# Linkwitz_Riley.net
KiCad netlist of a schematic drawn in Altium Designer
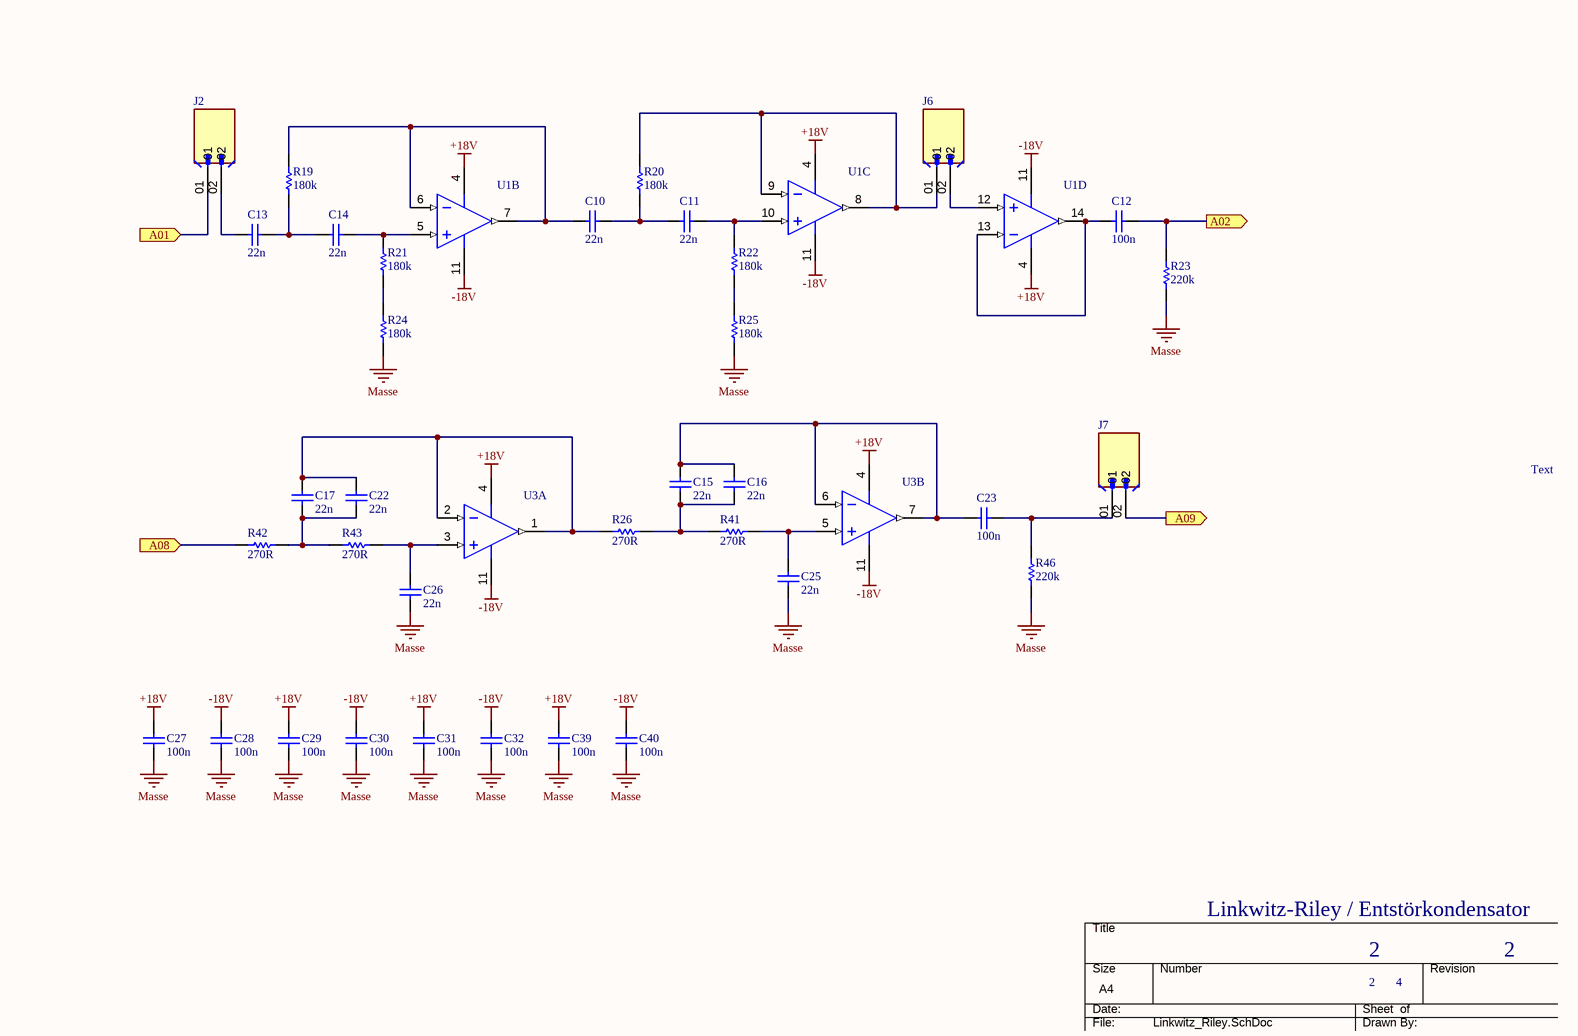
[diagram p0: Linkwitz_Riley.SchDoc]

(export (version "E")
  (design (tool "Eeschema 10.0.6"))
  (components
    (comp (ref "C10")
      (value "22n")
      (footprint "0805")
      (description "0805 Kondensator")
      (libsource (lib "Bauteile") (part "0805 Kondensator"))
    )
    (comp (ref "C11")
      (value "22n")
      (footprint "0805")
      (description "0805 Kondensator")
      (libsource (lib "Bauteile") (part "0805 Kondensator"))
    )
    (comp (ref "C12")
      (value "100n")
      (footprint "0805")
      (description "0805 Kondensator")
      (libsource (lib "Bauteile") (part "0805 Kondensator"))
    )
    (comp (ref "C13")
      (value "22n")
      (footprint "0805")
      (description "0805 Kondensator")
      (libsource (lib "Bauteile") (part "0805 Kondensator"))
    )
    (comp (ref "C14")
      (value "22n")
      (footprint "0805")
      (description "0805 Kondensator")
      (libsource (lib "Bauteile") (part "0805 Kondensator"))
    )
    (comp (ref "C15")
      (value "22n")
      (footprint "0805")
      (description "0805 Kondensator")
      (libsource (lib "Bauteile") (part "0805 Kondensator"))
    )
    (comp (ref "C16")
      (value "22n")
      (footprint "0805")
      (description "0805 Kondensator")
      (libsource (lib "Bauteile") (part "0805 Kondensator"))
    )
    (comp (ref "C17")
      (value "22n")
      (footprint "0805")
      (description "0805 Kondensator")
      (libsource (lib "Bauteile") (part "0805 Kondensator"))
    )
    (comp (ref "C22")
      (value "22n")
      (footprint "0805")
      (description "0805 Kondensator")
      (libsource (lib "Bauteile") (part "0805 Kondensator"))
    )
    (comp (ref "C23")
      (value "100n")
      (footprint "0805")
      (description "0805 Kondensator")
      (libsource (lib "Bauteile") (part "0805 Kondensator"))
    )
    (comp (ref "C25")
      (value "22n")
      (footprint "0805")
      (description "0805 Kondensator")
      (libsource (lib "Bauteile") (part "0805 Kondensator"))
    )
    (comp (ref "C26")
      (value "22n")
      (footprint "0805")
      (description "0805 Kondensator")
      (libsource (lib "Bauteile") (part "0805 Kondensator"))
    )
    (comp (ref "C27")
      (value "100n")
      (footprint "0805")
      (description "0805 Kondensator")
      (libsource (lib "Bauteile") (part "0805 Kondensator"))
    )
    (comp (ref "C28")
      (value "100n")
      (footprint "0805")
      (description "0805 Kondensator")
      (libsource (lib "Bauteile") (part "0805 Kondensator"))
    )
    (comp (ref "C29")
      (value "100n")
      (footprint "0805")
      (description "0805 Kondensator")
      (libsource (lib "Bauteile") (part "0805 Kondensator"))
    )
    (comp (ref "C30")
      (value "100n")
      (footprint "0805")
      (description "0805 Kondensator")
      (libsource (lib "Bauteile") (part "0805 Kondensator"))
    )
    (comp (ref "C31")
      (value "100n")
      (footprint "0805")
      (description "0805 Kondensator")
      (libsource (lib "Bauteile") (part "0805 Kondensator"))
    )
    (comp (ref "C32")
      (value "100n")
      (footprint "0805")
      (description "0805 Kondensator")
      (libsource (lib "Bauteile") (part "0805 Kondensator"))
    )
    (comp (ref "C39")
      (value "100n")
      (footprint "0805")
      (description "0805 Kondensator")
      (libsource (lib "Bauteile") (part "0805 Kondensator"))
    )
    (comp (ref "C40")
      (value "100n")
      (footprint "0805")
      (description "0805 Kondensator")
      (libsource (lib "Bauteile") (part "0805 Kondensator"))
    )
    (comp (ref "J2")
      (value "Connector x2")
      (footprint "Connector x2")
      (description "Connector Header Through Hole 2 position 0.100 (2.54mm)")
      (fields (field (name "MF") "Wurth Elektronik") (field (name "MP") "61300211121"))
      (libsource (lib "Bauteile") (part "Connector x2"))
    )
    (comp (ref "J6")
      (value "Connector x2")
      (footprint "Connector x2")
      (description "Connector Header Through Hole 2 position 0.100 (2.54mm)")
      (fields (field (name "MF") "Wurth Elektronik") (field (name "MP") "61300211121"))
      (libsource (lib "Bauteile") (part "Connector x2"))
    )
    (comp (ref "J7")
      (value "Connector x2")
      (footprint "Connector x2")
      (description "Connector Header Through Hole 2 position 0.100 (2.54mm)")
      (fields (field (name "MF") "Wurth Elektronik") (field (name "MP") "61300211121"))
      (libsource (lib "Bauteile") (part "Connector x2"))
    )
    (comp (ref "R19")
      (value "180k")
      (footprint "0805")
      (description "0805 Widerstand")
      (libsource (lib "Bauteile") (part "0805 Widerstand"))
    )
    (comp (ref "R20")
      (value "180k")
      (footprint "0805")
      (description "0805 Widerstand")
      (libsource (lib "Bauteile") (part "0805 Widerstand"))
    )
    (comp (ref "R21")
      (value "180k")
      (footprint "0805")
      (description "0805 Widerstand")
      (libsource (lib "Bauteile") (part "0805 Widerstand"))
    )
    (comp (ref "R22")
      (value "180k")
      (footprint "0805")
      (description "0805 Widerstand")
      (libsource (lib "Bauteile") (part "0805 Widerstand"))
    )
    (comp (ref "R23")
      (value "220k")
      (footprint "0805")
      (description "0805 Widerstand")
      (libsource (lib "Bauteile") (part "0805 Widerstand"))
    )
    (comp (ref "R24")
      (value "180k")
      (footprint "0805")
      (description "0805 Widerstand")
      (libsource (lib "Bauteile") (part "0805 Widerstand"))
    )
    (comp (ref "R25")
      (value "180k")
      (footprint "0805")
      (description "0805 Widerstand")
      (libsource (lib "Bauteile") (part "0805 Widerstand"))
    )
    (comp (ref "R26")
      (value "270R")
      (footprint "0805")
      (description "0805 Widerstand")
      (libsource (lib "Bauteile") (part "0805 Widerstand"))
    )
    (comp (ref "R41")
      (value "270R")
      (footprint "0805")
      (description "0805 Widerstand")
      (libsource (lib "Bauteile") (part "0805 Widerstand"))
    )
    (comp (ref "R42")
      (value "270R")
      (footprint "0805")
      (description "0805 Widerstand")
      (libsource (lib "Bauteile") (part "0805 Widerstand"))
    )
    (comp (ref "R43")
      (value "270R")
      (footprint "0805")
      (description "0805 Widerstand")
      (libsource (lib "Bauteile") (part "0805 Widerstand"))
    )
    (comp (ref "R46")
      (value "220k")
      (footprint "0805")
      (description "0805 Widerstand")
      (libsource (lib "Bauteile") (part "0805 Widerstand"))
    )
    (comp (ref "U1")
      (value "OPA4134UA")
      (footprint "DIP14 IC Socket")
      (fields (field (name "MANUFACTURER") "Texas Instruments"))
      (libsource (lib "Bauteile") (part "SOIC OPA4134UA"))
    )
    (comp (ref "U3")
      (value "OPA4134UA")
      (footprint "DIP14 IC Socket")
      (fields (field (name "MANUFACTURER") "Texas Instruments"))
      (libsource (lib "Bauteile") (part "SOIC OPA4134UA"))
    )
  )
  (nets
    (net (code "1") (name "+18V") (class "Default")
      (node (ref "C27") (pin "2") (pinfunction "2_2") (pintype "passive"))
      (node (ref "C29") (pin "2") (pinfunction "2_2") (pintype "passive"))
      (node (ref "C31") (pin "2") (pinfunction "2_2") (pintype "passive"))
      (node (ref "C39") (pin "2") (pinfunction "2_2") (pintype "passive"))
      (node (ref "U1") (pin "4") (pinfunction "V+_4") (pintype "power_in"))
      (node (ref "U3") (pin "4") (pinfunction "V+_4") (pintype "power_in"))
    )
    (net (code "2") (name "-18V") (class "Default")
      (node (ref "C28") (pin "2") (pinfunction "2_2") (pintype "passive"))
      (node (ref "C30") (pin "2") (pinfunction "2_2") (pintype "passive"))
      (node (ref "C32") (pin "2") (pinfunction "2_2") (pintype "passive"))
      (node (ref "C40") (pin "2") (pinfunction "2_2") (pintype "passive"))
      (node (ref "U1") (pin "11") (pinfunction "V-_11") (pintype "power_in"))
      (node (ref "U3") (pin "11") (pinfunction "V-_11") (pintype "power_in"))
    )
    (net (code "3") (name "/A01") (class "Default")
      (node (ref "J2") (pin "01") (pinfunction "01_01") (pintype "passive"))
    )
    (net (code "4") (name "/A02") (class "Default")
      (node (ref "C12") (pin "2") (pinfunction "2_2") (pintype "passive"))
      (node (ref "R23") (pin "2") (pinfunction "2_2") (pintype "passive"))
    )
    (net (code "5") (name "/A08") (class "Default")
      (node (ref "R42") (pin "2") (pinfunction "2_2") (pintype "passive"))
    )
    (net (code "6") (name "/A09") (class "Default")
      (node (ref "J7") (pin "02") (pinfunction "02_02") (pintype "passive"))
    )
    (net (code "7") (name "Masse") (class "Default")
      (node (ref "C25") (pin "1") (pinfunction "1_1") (pintype "passive"))
      (node (ref "C26") (pin "1") (pinfunction "1_1") (pintype "passive"))
      (node (ref "C27") (pin "1") (pinfunction "1_1") (pintype "passive"))
      (node (ref "C28") (pin "1") (pinfunction "1_1") (pintype "passive"))
      (node (ref "C29") (pin "1") (pinfunction "1_1") (pintype "passive"))
      (node (ref "C30") (pin "1") (pinfunction "1_1") (pintype "passive"))
      (node (ref "C31") (pin "1") (pinfunction "1_1") (pintype "passive"))
      (node (ref "C32") (pin "1") (pinfunction "1_1") (pintype "passive"))
      (node (ref "C39") (pin "1") (pinfunction "1_1") (pintype "passive"))
      (node (ref "C40") (pin "1") (pinfunction "1_1") (pintype "passive"))
      (node (ref "R23") (pin "1") (pinfunction "1_1") (pintype "passive"))
      (node (ref "R24") (pin "1") (pinfunction "1_1") (pintype "passive"))
      (node (ref "R25") (pin "1") (pinfunction "1_1") (pintype "passive"))
      (node (ref "R46") (pin "1") (pinfunction "1_1") (pintype "passive"))
    )
    (net (code "8") (name "Net-(C10-Pad2)") (class "Default")
      (node (ref "C10") (pin "2") (pinfunction "2_2") (pintype "passive"))
      (node (ref "C11") (pin "1") (pinfunction "1_1") (pintype "passive"))
      (node (ref "R20") (pin "1") (pinfunction "1_1") (pintype "passive"))
    )
    (net (code "9") (name "Net-(C13-Pad1)") (class "Default")
      (node (ref "C13") (pin "1") (pinfunction "1_1") (pintype "passive"))
      (node (ref "J2") (pin "02") (pinfunction "02_02") (pintype "passive"))
    )
    (net (code "10") (name "Net-(C13-Pad2)") (class "Default")
      (node (ref "C13") (pin "2") (pinfunction "2_2") (pintype "passive"))
      (node (ref "C14") (pin "1") (pinfunction "1_1") (pintype "passive"))
      (node (ref "R19") (pin "1") (pinfunction "1_1") (pintype "passive"))
    )
    (net (code "11") (name "Net-(C15-Pad1)") (class "Default")
      (node (ref "C15") (pin "1") (pinfunction "1_1") (pintype "passive"))
      (node (ref "C16") (pin "1") (pinfunction "1_1") (pintype "passive"))
      (node (ref "R26") (pin "1") (pinfunction "1_1") (pintype "passive"))
      (node (ref "R41") (pin "2") (pinfunction "2_2") (pintype "passive"))
    )
    (net (code "12") (name "Net-(C17-Pad1)") (class "Default")
      (node (ref "C17") (pin "1") (pinfunction "1_1") (pintype "passive"))
      (node (ref "C22") (pin "1") (pinfunction "1_1") (pintype "passive"))
      (node (ref "R42") (pin "1") (pinfunction "1_1") (pintype "passive"))
      (node (ref "R43") (pin "2") (pinfunction "2_2") (pintype "passive"))
    )
    (net (code "13") (name "Net-(C23-Pad2)") (class "Default")
      (node (ref "C23") (pin "2") (pinfunction "2_2") (pintype "passive"))
      (node (ref "J7") (pin "01") (pinfunction "01_01") (pintype "passive"))
      (node (ref "R46") (pin "2") (pinfunction "2_2") (pintype "passive"))
    )
    (net (code "14") (name "Net-(R21-Pad1)") (class "Default")
      (node (ref "R21") (pin "1") (pinfunction "1_1") (pintype "passive"))
      (node (ref "R24") (pin "2") (pinfunction "2_2") (pintype "passive"))
    )
    (net (code "15") (name "Net-(R22-Pad1)") (class "Default")
      (node (ref "R22") (pin "1") (pinfunction "1_1") (pintype "passive"))
      (node (ref "R25") (pin "2") (pinfunction "2_2") (pintype "passive"))
    )
    (net (code "16") (name "Net-(U1B-IN_B+)") (class "Default")
      (node (ref "C14") (pin "2") (pinfunction "2_2") (pintype "passive"))
      (node (ref "R21") (pin "2") (pinfunction "2_2") (pintype "passive"))
      (node (ref "U1") (pin "5") (pinfunction "IN_B+_5") (pintype "input"))
    )
    (net (code "17") (name "Net-(U1B-IN_B-)") (class "Default")
      (node (ref "C10") (pin "1") (pinfunction "1_1") (pintype "passive"))
      (node (ref "R19") (pin "2") (pinfunction "2_2") (pintype "passive"))
      (node (ref "U1") (pin "6") (pinfunction "IN_B-_6") (pintype "input"))
      (node (ref "U1") (pin "7") (pinfunction "OUT_B_7") (pintype "output"))
    )
    (net (code "18") (name "Net-(U1C-IN_C+)") (class "Default")
      (node (ref "C11") (pin "2") (pinfunction "2_2") (pintype "passive"))
      (node (ref "R22") (pin "2") (pinfunction "2_2") (pintype "passive"))
      (node (ref "U1") (pin "10") (pinfunction "IN_C+_10") (pintype "input"))
    )
    (net (code "19") (name "Net-(U1C-IN_C-)") (class "Default")
      (node (ref "J6") (pin "01") (pinfunction "01_01") (pintype "passive"))
      (node (ref "R20") (pin "2") (pinfunction "2_2") (pintype "passive"))
      (node (ref "U1") (pin "8") (pinfunction "OUT_C_8") (pintype "output"))
      (node (ref "U1") (pin "9") (pinfunction "IN_C-_9") (pintype "input"))
    )
    (net (code "20") (name "Net-(U1D-IN_D+)") (class "Default")
      (node (ref "J6") (pin "02") (pinfunction "02_02") (pintype "passive"))
      (node (ref "U1") (pin "12") (pinfunction "IN_D+_12") (pintype "input"))
    )
    (net (code "21") (name "Net-(U1D-IN_D-)") (class "Default")
      (node (ref "C12") (pin "1") (pinfunction "1_1") (pintype "passive"))
      (node (ref "U1") (pin "13") (pinfunction "IN_D-_13") (pintype "input"))
      (node (ref "U1") (pin "14") (pinfunction "OUT_D_14") (pintype "output"))
    )
    (net (code "22") (name "Net-(U3A-IN_A+)") (class "Default")
      (node (ref "C26") (pin "2") (pinfunction "2_2") (pintype "passive"))
      (node (ref "R43") (pin "1") (pinfunction "1_1") (pintype "passive"))
      (node (ref "U3") (pin "3") (pinfunction "IN_A+_3") (pintype "input"))
    )
    (net (code "23") (name "Net-(U3A-IN_A-)") (class "Default")
      (node (ref "C17") (pin "2") (pinfunction "2_2") (pintype "passive"))
      (node (ref "C22") (pin "2") (pinfunction "2_2") (pintype "passive"))
      (node (ref "R26") (pin "2") (pinfunction "2_2") (pintype "passive"))
      (node (ref "U3") (pin "1") (pinfunction "OUT_A_1") (pintype "output"))
      (node (ref "U3") (pin "2") (pinfunction "IN_A-_2") (pintype "input"))
    )
    (net (code "24") (name "Net-(U3B-IN_B+)") (class "Default")
      (node (ref "C25") (pin "2") (pinfunction "2_2") (pintype "passive"))
      (node (ref "R41") (pin "1") (pinfunction "1_1") (pintype "passive"))
      (node (ref "U3") (pin "5") (pinfunction "IN_B+_5") (pintype "input"))
    )
    (net (code "25") (name "Net-(U3B-IN_B-)") (class "Default")
      (node (ref "C15") (pin "2") (pinfunction "2_2") (pintype "passive"))
      (node (ref "C16") (pin "2") (pinfunction "2_2") (pintype "passive"))
      (node (ref "C23") (pin "1") (pinfunction "1_1") (pintype "passive"))
      (node (ref "U3") (pin "6") (pinfunction "IN_B-_6") (pintype "input"))
      (node (ref "U3") (pin "7") (pinfunction "OUT_B_7") (pintype "output"))
    )
  )
)
